# MZ.net
KiCad netlist of a schematic drawn in Altium Designer
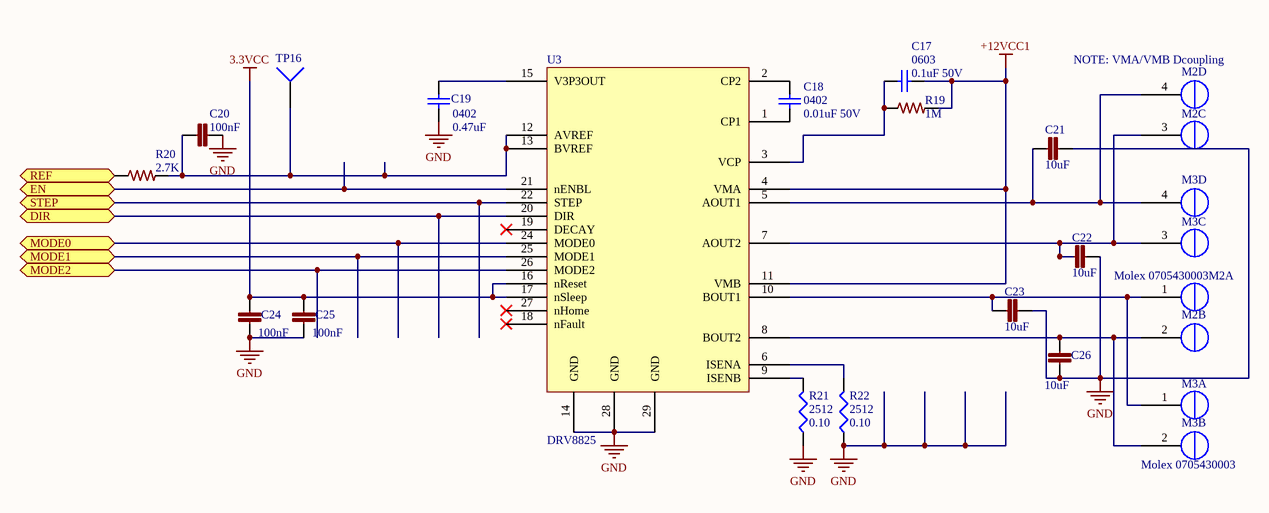
[diagram p0: MZ.SchDoc]

(export (version "E")
  (design (tool "Eeschema 10.0.6"))
  (components
    (comp (ref "C17")
      (value "0603")
      (footprint "1608[0603]")
      (description "Capacitor (Semiconductor SIM Model)")
      (fields (field (name "ALTIUM_VALUE") "0.1uF 50V") (field (name "PUBLISHER") "Altium Limited"))
      (libsource (lib "Miscellaneous Devices") (part "Cap Semi"))
    )
    (comp (ref "C18")
      (value "0.01uF 50V")
      (footprint "C0402")
      (description "CAP CER 10000PF 50V X7R 0402")
      (fields
        (field (name "MFR PART #") "GRM155R71H103JA88D")
        (field (name "MFR") "Murata")
        (field (name "PACKAGEREFERENCE") "0402")
        (field (name "PUBLISHER") "Ultimachine")
      )
      (libsource (lib "Tigershark3D") (part "GRM155R71H103JA88D"))
    )
    (comp (ref "C19")
      (value "0.47uF")
      (footprint "C0402")
      (description "0.47uF 6.3v C0402 - GRM155R60J474KE19D")
      (fields
        (field (name "MFR PART #") "GRM155R60J474KE19D")
        (field (name "MFR") "Murata")
        (field (name "PACKAGEREFERENCE") "0402")
        (field (name "PUBLISHER") "Ultimachine")
      )
      (libsource (lib "Tigershark3D") (part "GRM155R60J474KE19D"))
    )
    (comp (ref "C20")
      (value "100nF")
      (footprint "C0402")
      (description "CAP CER 0402 100nF 16V 10% X7R")
      (fields
        (field (name "MANUFACTURERPARTNUMBER") "GRM155R71C104KA88D")
        (field (name "PUBLISHER") "UltiMachine")
      )
      (libsource (lib "3Delight") (part "GRM155R71C104KA88D"))
    )
    (comp (ref "C21")
      (value "10uF")
      (footprint "C0603")
      (description "CAP CER 0603 1uF 10V Y5V")
      (fields
        (field (name "MANUFACTURERPARTNUMBER") "CC0603ZRY5V6BB105")
        (field (name "PUBLISHER") "UltiMachine")
      )
      (libsource (lib "") (part "CC0603ZRY5V6BB105_1"))
    )
    (comp (ref "C22")
      (value "10uF")
      (footprint "C0603")
      (description "CAP CER 0603 1uF 10V Y5V")
      (fields
        (field (name "MANUFACTURERPARTNUMBER") "CC0603ZRY5V6BB105")
        (field (name "PUBLISHER") "UltiMachine")
      )
      (libsource (lib "") (part "CC0603ZRY5V6BB105_1"))
    )
    (comp (ref "C23")
      (value "10uF")
      (footprint "C0603")
      (description "CAP CER 0603 1uF 10V Y5V")
      (fields
        (field (name "MANUFACTURERPARTNUMBER") "CC0603ZRY5V6BB105")
        (field (name "PUBLISHER") "UltiMachine")
      )
      (libsource (lib "") (part "CC0603ZRY5V6BB105_1"))
    )
    (comp (ref "C24")
      (value "100nF")
      (footprint "C0402")
      (description "CAP CER 0402 100nF 16V 10% X7R")
      (fields
        (field (name "MANUFACTURERPARTNUMBER") "GRM155R71C104KA88D")
        (field (name "PUBLISHER") "UltiMachine")
      )
      (libsource (lib "") (part "GRM155R71C104KA88D_1"))
    )
    (comp (ref "C25")
      (value "100nF")
      (footprint "C0402")
      (description "CAP CER 0402 100nF 16V 10% X7R")
      (fields
        (field (name "MANUFACTURERPARTNUMBER") "GRM155R71C104KA88D")
        (field (name "PUBLISHER") "UltiMachine")
      )
      (libsource (lib "") (part "GRM155R71C104KA88D_1"))
    )
    (comp (ref "C26")
      (value "10uF")
      (footprint "C0603")
      (description "CAP CER 0603 1uF 10V Y5V")
      (fields
        (field (name "MANUFACTURERPARTNUMBER") "CC0603ZRY5V6BB105")
        (field (name "PUBLISHER") "UltiMachine")
      )
      (libsource (lib "Tigershark3D") (part "CC0603ZRY5V6BB105"))
    )
    (comp (ref "M2")
      (value "Molex 0705430003")
      (footprint "4POL254")
      (description "Molex 4 Pin Clip Connector")
      (libsource (lib "ZMBo Schematic Library") (part "Molex 0705430003 Alt"))
    )
    (comp (ref "M3")
      (value "Molex 0705430003")
      (footprint "Molex 0705430003")
      (description "Molex 4 Pin Clip Connector")
      (libsource (lib "ZMBo Schematic Library") (part "Molex 0705430003 Alt"))
    )
    (comp (ref "R19")
      (value "1M")
      (footprint "R0402")
      (description "RES 0402 1M 100mW 5%")
      (fields (field (name "MANUFACTURERPARTNUMBER") "ERJ2GEJ105X") (field (name "PUBLISHER") "UltiMachine"))
      (libsource (lib "Tigershark3D") (part "ERJ2GEJ105X"))
    )
    (comp (ref "R20")
      (value "2.7K")
      (footprint "R0402")
      (description "RES SMD 2.7K OHM 1% 1/10W 0402")
      (fields
        (field (name "MANUFACTURER") "Panasonic")
        (field (name "MANUFACTURERPARTNUMBER") "ERJ2GEJ105X")
        (field (name "PUBLISHER") "Adam")
      )
      (libsource (lib "Tigershark3D") (part "ERJ-2RKF2701X"))
    )
    (comp (ref "R21")
      (value "2512")
      (footprint "2512R-0.55")
      (description "RES SMD 0.1 OHM 1% 2W 2512")
      (fields (field (name "MFR") "Stackpole ELectronics Inc") (field (name "ALTIUM_VALUE") "0.10"))
      (libsource (lib "Tigershark3D") (part "CSRN2512FTR100"))
    )
    (comp (ref "R22")
      (value "2512")
      (footprint "2512R-0.55")
      (description "RES SMD 0.1 OHM 1% 2W 2512")
      (fields (field (name "MFR") "Stackpole ELectronics Inc") (field (name "ALTIUM_VALUE") "0.10"))
      (libsource (lib "Tigershark3D") (part "CSRN2512FTR100"))
    )
    (comp (ref "TP16")
      (value "TP4")
      (footprint "TP-2")
      (description "Socket")
      (fields (field (name "PUBLISHER") "Altium Limited"))
      (libsource (lib "ZMBo Schematic Library") (part "Socket"))
    )
    (comp (ref "U3")
      (value "DRV8825")
      (footprint "DRV8825PWPR")
      (description "DRV8825 Ti Stepper Driver")
      (fields (field (name "PART NUMBER") "DRV8825PWPR") (field (name "VOLTAGE") "8.2-45VDC"))
      (libsource (lib "Tigershark3D") (part "DRV8825"))
    )
  )
  (nets
    (net (code "1") (name "+12VCC1") (class "Default")
      (node (ref "C17") (pin "1") (pinfunction "1_1") (pintype "passive"))
      (node (ref "R19") (pin "2") (pinfunction "2_2") (pintype "passive"))
      (node (ref "U3") (pin "11") (pinfunction "VMB_11") (pintype "passive"))
      (node (ref "U3") (pin "4") (pinfunction "VMA_4") (pintype "passive"))
    )
    (net (code "2") (name "/DIR") (class "Default")
      (node (ref "U3") (pin "20") (pinfunction "DIR_20") (pintype "passive"))
    )
    (net (code "3") (name "/EN") (class "Default")
      (node (ref "U3") (pin "21") (pinfunction "nENBL_21") (pintype "passive"))
    )
    (net (code "4") (name "/MODE0") (class "Default")
      (node (ref "U3") (pin "24") (pinfunction "MODE0_24") (pintype "passive"))
    )
    (net (code "5") (name "/MODE1") (class "Default")
      (node (ref "U3") (pin "25") (pinfunction "MODE1_25") (pintype "passive"))
    )
    (net (code "6") (name "/MODE2") (class "Default")
      (node (ref "U3") (pin "26") (pinfunction "MODE2_26") (pintype "passive"))
    )
    (net (code "7") (name "/REF") (class "Default")
      (node (ref "R20") (pin "1") (pinfunction "1_1") (pintype "passive"))
    )
    (net (code "8") (name "/STEP") (class "Default")
      (node (ref "U3") (pin "22") (pinfunction "STEP_22") (pintype "passive"))
    )
    (net (code "9") (name "3.3VCC") (class "Default")
      (node (ref "C24") (pin "1") (pinfunction "1_1") (pintype "passive"))
      (node (ref "C25") (pin "1") (pinfunction "1_1") (pintype "passive"))
      (node (ref "U3") (pin "16") (pinfunction "nReset_16") (pintype "passive"))
      (node (ref "U3") (pin "17") (pinfunction "nSleep_17") (pintype "passive"))
    )
    (net (code "10") (name "GND") (class "Default")
      (node (ref "C19") (pin "1") (pinfunction "1_1") (pintype "passive"))
      (node (ref "C20") (pin "2") (pinfunction "2_2") (pintype "passive"))
      (node (ref "C21") (pin "2") (pinfunction "2_2") (pintype "passive"))
      (node (ref "C22") (pin "2") (pinfunction "2_2") (pintype "passive"))
      (node (ref "C23") (pin "2") (pinfunction "2_2") (pintype "passive"))
      (node (ref "C24") (pin "2") (pinfunction "2_2") (pintype "passive"))
      (node (ref "C25") (pin "2") (pinfunction "2_2") (pintype "passive"))
      (node (ref "C26") (pin "2") (pinfunction "2_2") (pintype "passive"))
      (node (ref "R21") (pin "1") (pinfunction "1_1") (pintype "passive"))
      (node (ref "R22") (pin "1") (pinfunction "1_1") (pintype "passive"))
      (node (ref "U3") (pin "14") (pinfunction "GND_14") (pintype "passive"))
      (node (ref "U3") (pin "28") (pinfunction "GND_28") (pintype "passive"))
      (node (ref "U3") (pin "29") (pinfunction "GND_29") (pintype "passive"))
    )
    (net (code "11") (name "Net-(M2A-OUT2B)") (class "Default")
      (node (ref "C23") (pin "1") (pinfunction "1_1") (pintype "passive"))
      (node (ref "M2") (pin "1") (pinfunction "OUT2B_1") (pintype "passive"))
      (node (ref "M3") (pin "1") (pinfunction "OUT2B_1") (pintype "passive"))
      (node (ref "U3") (pin "10") (pinfunction "BOUT1_10") (pintype "passive"))
    )
    (net (code "12") (name "Net-(M2B-OUT2A)") (class "Default")
      (node (ref "C26") (pin "1") (pinfunction "1_1") (pintype "passive"))
      (node (ref "M2") (pin "2") (pinfunction "OUT2A_2") (pintype "passive"))
      (node (ref "M3") (pin "2") (pinfunction "OUT2A_2") (pintype "passive"))
      (node (ref "U3") (pin "8") (pinfunction "BOUT2_8") (pintype "passive"))
    )
    (net (code "13") (name "Net-(M2C-OUT1A)") (class "Default")
      (node (ref "C22") (pin "1") (pinfunction "1_1") (pintype "passive"))
      (node (ref "M2") (pin "3") (pinfunction "OUT1A_3") (pintype "passive"))
      (node (ref "M3") (pin "3") (pinfunction "OUT1A_3") (pintype "passive"))
      (node (ref "U3") (pin "7") (pinfunction "AOUT2_7") (pintype "passive"))
    )
    (net (code "14") (name "Net-(M2D-OUT1B)") (class "Default")
      (node (ref "C21") (pin "1") (pinfunction "1_1") (pintype "passive"))
      (node (ref "M2") (pin "4") (pinfunction "OUT1B_4") (pintype "passive"))
      (node (ref "M3") (pin "4") (pinfunction "OUT1B_4") (pintype "passive"))
      (node (ref "U3") (pin "5") (pinfunction "AOUT1_5") (pintype "passive"))
    )
    (net (code "15") (name "Net-(U3-AVREF)") (class "Default")
      (node (ref "C20") (pin "1") (pinfunction "1_1") (pintype "passive"))
      (node (ref "R20") (pin "2") (pinfunction "2_2") (pintype "passive"))
      (node (ref "TP16") (pin "1") (pinfunction "1_1") (pintype "passive"))
      (node (ref "U3") (pin "12") (pinfunction "AVREF_12") (pintype "passive"))
      (node (ref "U3") (pin "13") (pinfunction "BVREF_13") (pintype "passive"))
    )
    (net (code "16") (name "Net-(U3-CP1)") (class "Default")
      (node (ref "C18") (pin "1") (pinfunction "1_1") (pintype "passive"))
      (node (ref "U3") (pin "1") (pinfunction "CP1_1") (pintype "passive"))
    )
    (net (code "17") (name "Net-(U3-CP2)") (class "Default")
      (node (ref "C18") (pin "2") (pinfunction "2_2") (pintype "passive"))
      (node (ref "U3") (pin "2") (pinfunction "CP2_2") (pintype "passive"))
    )
    (net (code "18") (name "Net-(U3-ISENA)") (class "Default")
      (node (ref "R22") (pin "2") (pinfunction "2_2") (pintype "passive"))
      (node (ref "U3") (pin "6") (pinfunction "ISENA_6") (pintype "passive"))
    )
    (net (code "19") (name "Net-(U3-ISENB)") (class "Default")
      (node (ref "R21") (pin "2") (pinfunction "2_2") (pintype "passive"))
      (node (ref "U3") (pin "9") (pinfunction "ISENB_9") (pintype "passive"))
    )
    (net (code "20") (name "Net-(U3-V3P3OUT)") (class "Default")
      (node (ref "C19") (pin "2") (pinfunction "2_2") (pintype "passive"))
      (node (ref "U3") (pin "15") (pinfunction "V3P3OUT_15") (pintype "passive"))
    )
    (net (code "21") (name "Net-(U3-VCP)") (class "Default")
      (node (ref "C17") (pin "2") (pinfunction "2_2") (pintype "passive"))
      (node (ref "R19") (pin "1") (pinfunction "1_1") (pintype "passive"))
      (node (ref "U3") (pin "3") (pinfunction "VCP_3") (pintype "passive"))
    )
    (net (code "22") (name "unconnected-(U3-DECAY-Pad19)") (class "Default")
      (node (ref "U3") (pin "19") (pinfunction "DECAY_19") (pintype "passive+no_connect"))
    )
    (net (code "23") (name "unconnected-(U3-NC-Pad23)") (class "Default")
      (node (ref "U3") (pin "23") (pinfunction "NC_23") (pintype "passive"))
    )
    (net (code "24") (name "unconnected-(U3-nFault-Pad18)") (class "Default")
      (node (ref "U3") (pin "18") (pinfunction "nFault_18") (pintype "passive+no_connect"))
    )
    (net (code "25") (name "unconnected-(U3-nHome-Pad27)") (class "Default")
      (node (ref "U3") (pin "27") (pinfunction "nHome_27") (pintype "passive+no_connect"))
    )
  )
)
